# hermes_prog.net
KiCad netlist of a schematic drawn in EAGLE
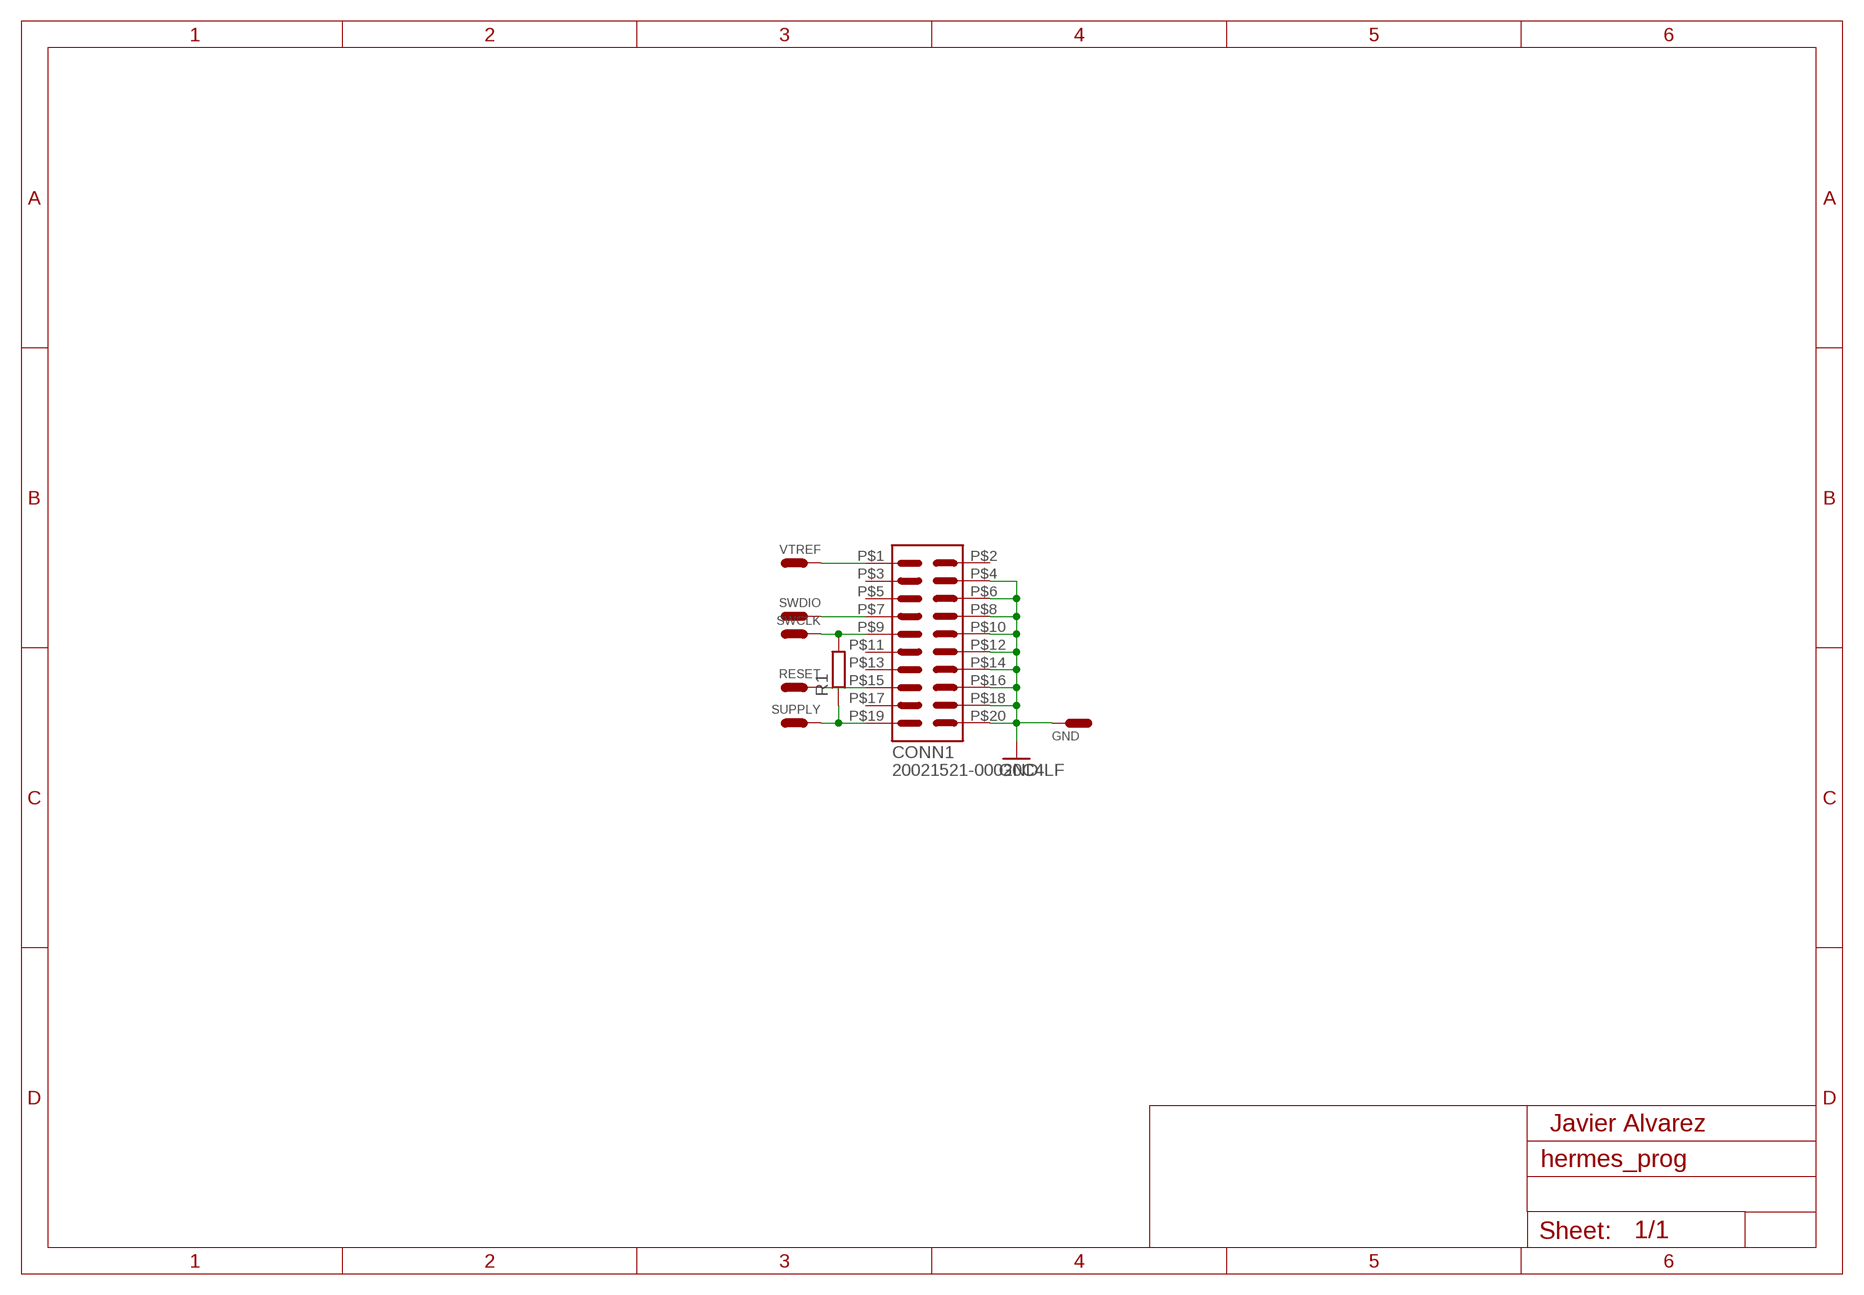
[diagram p0: schematic, sheet 1]

(export (version "E")
  (design (tool "Eeschema 10.0.6"))
  (components
    (comp (ref "CONN1")
      (value "20021521-00020C4LF")
      (footprint "eagle-import:JTAG-20")
      (libsource (lib "eagle-import") (part "20021521-00020C4LF"))
    )
    (comp (ref "GND")
      (value "S7231-45R")
      (footprint "eagle-import:SPRING-CONTACT")
      (libsource (lib "eagle-import") (part "S7231-45R"))
    )
    (comp (ref "R1")
      (value "R-EU_0204/2V")
      (footprint "eagle-import:0204V")
      (libsource (lib "eagle-import") (part "R-EU_0204/2V"))
    )
    (comp (ref "RESET")
      (value "S7231-45R")
      (footprint "eagle-import:SPRING-CONTACT")
      (libsource (lib "eagle-import") (part "S7231-45R"))
    )
    (comp (ref "SUPPLY")
      (value "S7231-45R")
      (footprint "eagle-import:SPRING-CONTACT")
      (libsource (lib "eagle-import") (part "S7231-45R"))
    )
    (comp (ref "SWCLK")
      (value "S7231-45R")
      (footprint "eagle-import:SPRING-CONTACT")
      (libsource (lib "eagle-import") (part "S7231-45R"))
    )
    (comp (ref "SWDIO")
      (value "S7231-45R")
      (footprint "eagle-import:SPRING-CONTACT")
      (libsource (lib "eagle-import") (part "S7231-45R"))
    )
    (comp (ref "VTREF")
      (value "S7231-45R")
      (footprint "eagle-import:SPRING-CONTACT")
      (libsource (lib "eagle-import") (part "S7231-45R"))
    )
  )
  (nets
    (net (code "1") (name "GND") (class "Default")
      (node (ref "CONN1") (pin "P$10") (pinfunction "P$10_P$10") (pintype "bidirectional"))
      (node (ref "CONN1") (pin "P$12") (pinfunction "P$12_P$12") (pintype "bidirectional"))
      (node (ref "CONN1") (pin "P$14") (pinfunction "P$14_P$14") (pintype "bidirectional"))
      (node (ref "CONN1") (pin "P$16") (pinfunction "P$16_P$16") (pintype "bidirectional"))
      (node (ref "CONN1") (pin "P$18") (pinfunction "P$18_P$18") (pintype "bidirectional"))
      (node (ref "CONN1") (pin "P$20") (pinfunction "P$20_P$20") (pintype "bidirectional"))
      (node (ref "CONN1") (pin "P$4") (pinfunction "P$4_P$4") (pintype "bidirectional"))
      (node (ref "CONN1") (pin "P$6") (pinfunction "P$6_P$6") (pintype "bidirectional"))
      (node (ref "CONN1") (pin "P$8") (pinfunction "P$8_P$8") (pintype "bidirectional"))
      (node (ref "GND") (pin "P$1") (pinfunction "P$1_P$1") (pintype "bidirectional"))
      (node (ref "GND") (pin "P$2") (pinfunction "P$1_P$2") (pintype "bidirectional"))
    )
    (net (code "2") (name "Net-(CONN1-PadP$1)") (class "Default")
      (node (ref "CONN1") (pin "P$1") (pinfunction "P$1_P$1") (pintype "bidirectional"))
      (node (ref "VTREF") (pin "P$1") (pinfunction "P$1_P$1") (pintype "bidirectional"))
      (node (ref "VTREF") (pin "P$2") (pinfunction "P$1_P$2") (pintype "bidirectional"))
    )
    (net (code "3") (name "Net-(CONN1-PadP$7)") (class "Default")
      (node (ref "CONN1") (pin "P$7") (pinfunction "P$7_P$7") (pintype "bidirectional"))
      (node (ref "SWDIO") (pin "P$1") (pinfunction "P$1_P$1") (pintype "bidirectional"))
      (node (ref "SWDIO") (pin "P$2") (pinfunction "P$1_P$2") (pintype "bidirectional"))
    )
    (net (code "4") (name "Net-(CONN1-PadP$9)") (class "Default")
      (node (ref "CONN1") (pin "P$9") (pinfunction "P$9_P$9") (pintype "bidirectional"))
      (node (ref "R1") (pin "2") (pinfunction "2_2") (pintype "passive"))
      (node (ref "SWCLK") (pin "P$1") (pinfunction "P$1_P$1") (pintype "bidirectional"))
      (node (ref "SWCLK") (pin "P$2") (pinfunction "P$1_P$2") (pintype "bidirectional"))
    )
    (net (code "5") (name "Net-(CONN1-PadP$15)") (class "Default")
      (node (ref "CONN1") (pin "P$15") (pinfunction "P$15_P$15") (pintype "bidirectional"))
      (node (ref "RESET") (pin "P$1") (pinfunction "P$1_P$1") (pintype "bidirectional"))
      (node (ref "RESET") (pin "P$2") (pinfunction "P$1_P$2") (pintype "bidirectional"))
    )
    (net (code "6") (name "Net-(CONN1-PadP$19)") (class "Default")
      (node (ref "CONN1") (pin "P$19") (pinfunction "P$19_P$19") (pintype "bidirectional"))
      (node (ref "R1") (pin "1") (pinfunction "1_1") (pintype "passive"))
      (node (ref "SUPPLY") (pin "P$1") (pinfunction "P$1_P$1") (pintype "bidirectional"))
      (node (ref "SUPPLY") (pin "P$2") (pinfunction "P$1_P$2") (pintype "bidirectional"))
    )
    (net (code "7") (name "unconnected-(CONN1-PadP$2)") (class "Default")
      (node (ref "CONN1") (pin "P$2") (pinfunction "P$2_P$2") (pintype "bidirectional"))
    )
    (net (code "8") (name "unconnected-(CONN1-PadP$3)") (class "Default")
      (node (ref "CONN1") (pin "P$3") (pinfunction "P$3_P$3") (pintype "bidirectional"))
    )
    (net (code "9") (name "unconnected-(CONN1-PadP$5)") (class "Default")
      (node (ref "CONN1") (pin "P$5") (pinfunction "P$5_P$5") (pintype "bidirectional"))
    )
    (net (code "10") (name "unconnected-(CONN1-PadP$11)") (class "Default")
      (node (ref "CONN1") (pin "P$11") (pinfunction "P$11_P$11") (pintype "bidirectional"))
    )
    (net (code "11") (name "unconnected-(CONN1-PadP$13)") (class "Default")
      (node (ref "CONN1") (pin "P$13") (pinfunction "P$13_P$13") (pintype "bidirectional"))
    )
    (net (code "12") (name "unconnected-(CONN1-PadP$17)") (class "Default")
      (node (ref "CONN1") (pin "P$17") (pinfunction "P$17_P$17") (pintype "bidirectional"))
    )
  )
)
